# TPT02.net
KiCad netlist of a schematic drawn in EAGLE
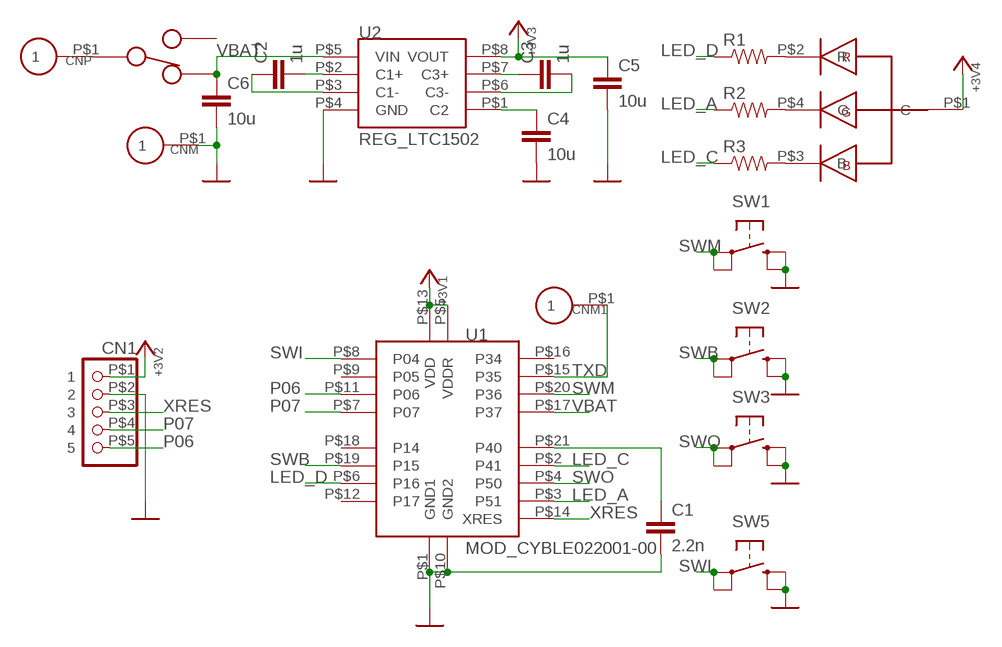
[diagram p0: schematic, sheet 1]

(export (version "E")
  (design (tool "Eeschema 10.0.6"))
  (components
    (comp (ref "C1")
      (value "2.2n")
      (footprint "eagle-import:0603")
      (libsource (lib "eagle-import") (part "CAP0603"))
    )
    (comp (ref "C2")
      (value "1u")
      (footprint "eagle-import:0603")
      (libsource (lib "eagle-import") (part "CAP0603"))
    )
    (comp (ref "C3")
      (value "1u")
      (footprint "eagle-import:0603")
      (libsource (lib "eagle-import") (part "CAP0603"))
    )
    (comp (ref "C4")
      (value "10u")
      (footprint "eagle-import:0603")
      (libsource (lib "eagle-import") (part "CAP0603"))
    )
    (comp (ref "C5")
      (value "10u")
      (footprint "eagle-import:0603")
      (libsource (lib "eagle-import") (part "CAP0603"))
    )
    (comp (ref "C6")
      (value "10u")
      (footprint "eagle-import:0603")
      (libsource (lib "eagle-import") (part "CAP0603"))
    )
    (comp (ref "CN1")
      (value "CON_PINHD-1X550MIL")
      (footprint "eagle-import:1X5_50MIL")
      (libsource (lib "eagle-import") (part "CON_PINHD-1X550MIL"))
    )
    (comp (ref "CNM")
      (value "CON_P01SMD1MM")
      (footprint "eagle-import:PAD_SMD1MM")
      (libsource (lib "eagle-import") (part "CON_P01SMD1MM"))
    )
    (comp (ref "CNM1")
      (value "CON_P01SMD1MM")
      (footprint "eagle-import:PAD_SMD1MM")
      (libsource (lib "eagle-import") (part "CON_P01SMD1MM"))
    )
    (comp (ref "CNP")
      (value "CON_P01SMD1MM")
      (footprint "eagle-import:PAD_SMD1MM")
      (libsource (lib "eagle-import") (part "CON_P01SMD1MM"))
    )
    (comp (ref "D1")
      (value "LED_RGB_OSTB0603C1C")
      (footprint "eagle-import:LED_0606_4P")
      (libsource (lib "eagle-import") (part "LED_RGB_OSTB0603C1C"))
    )
    (comp (ref "R1")
      (value "RES0603")
      (footprint "eagle-import:0603")
      (libsource (lib "eagle-import") (part "RES0603"))
    )
    (comp (ref "R2")
      (value "RES0603")
      (footprint "eagle-import:0603")
      (libsource (lib "eagle-import") (part "RES0603"))
    )
    (comp (ref "R3")
      (value "RES0603")
      (footprint "eagle-import:0603")
      (libsource (lib "eagle-import") (part "RES0603"))
    )
    (comp (ref "SW1")
      (value "SW_TACTEVQP2")
      (footprint "eagle-import:SW_EVQP2")
      (libsource (lib "eagle-import") (part "SW_TACTEVQP2"))
    )
    (comp (ref "SW2")
      (value "SW_TACTPTS525SK08")
      (footprint "eagle-import:SW_PTS525SK08")
      (libsource (lib "eagle-import") (part "SW_TACTPTS525SK08"))
    )
    (comp (ref "SW3")
      (value "SW_TACTPTS525SK08")
      (footprint "eagle-import:SW_PTS525SK08")
      (libsource (lib "eagle-import") (part "SW_TACTPTS525SK08"))
    )
    (comp (ref "SW4")
      (value "SW_SLIDECUS12")
      (footprint "eagle-import:SW_CUS-12B")
      (libsource (lib "eagle-import") (part "SW_SLIDECUS12"))
    )
    (comp (ref "SW5")
      (value "SW_TACTEVQPU02")
      (footprint "eagle-import:SW_EVQPUA02")
      (libsource (lib "eagle-import") (part "SW_TACTEVQPU02"))
    )
    (comp (ref "U1")
      (value "MOD_CYBLE022001-00")
      (footprint "eagle-import:MOD_CYBLE022001-00")
      (libsource (lib "eagle-import") (part "MOD_CYBLE022001-00"))
    )
    (comp (ref "U2")
      (value "REG_LTC1502")
      (footprint "eagle-import:MSOP8")
      (libsource (lib "eagle-import") (part "REG_LTC1502"))
    )
  )
  (nets
    (net (code "1") (name "/LED_A") (class "Default")
      (node (ref "R2") (pin "1") (pinfunction "1_1") (pintype "passive"))
      (node (ref "U1") (pin "P$3") (pinfunction "P51_P$3") (pintype "bidirectional"))
    )
    (net (code "2") (name "/LED_C") (class "Default")
      (node (ref "R3") (pin "1") (pinfunction "1_1") (pintype "passive"))
      (node (ref "U1") (pin "P$2") (pinfunction "P41_P$2") (pintype "bidirectional"))
    )
    (net (code "3") (name "/LED_D") (class "Default")
      (node (ref "R1") (pin "1") (pinfunction "1_1") (pintype "passive"))
      (node (ref "U1") (pin "P$6") (pinfunction "P16_P$6") (pintype "bidirectional"))
    )
    (net (code "4") (name "/P$3") (class "Default")
      (node (ref "SW4") (pin "P$3") (pinfunction "P$3_P$3") (pintype "power_in"))
    )
    (net (code "5") (name "/P06") (class "Default")
      (node (ref "CN1") (pin "P$5") (pinfunction "5_P$5") (pintype "passive"))
      (node (ref "U1") (pin "P$11") (pinfunction "P06_P$11") (pintype "bidirectional"))
    )
    (net (code "6") (name "/P07") (class "Default")
      (node (ref "CN1") (pin "P$4") (pinfunction "4_P$4") (pintype "passive"))
      (node (ref "U1") (pin "P$7") (pinfunction "P07_P$7") (pintype "bidirectional"))
    )
    (net (code "7") (name "/SWB") (class "Default")
      (node (ref "SW2") (pin "P$A1") (pinfunction "P_P$A1") (pintype "passive"))
      (node (ref "SW2") (pin "P$A2") (pinfunction "P1_P$A2") (pintype "passive"))
      (node (ref "U1") (pin "P$19") (pinfunction "P15_P$19") (pintype "bidirectional"))
    )
    (net (code "8") (name "/SWI") (class "Default")
      (node (ref "SW5") (pin "PA1") (pinfunction "P_PA1") (pintype "passive"))
      (node (ref "SW5") (pin "PA2") (pinfunction "P1_PA2") (pintype "passive"))
      (node (ref "U1") (pin "P$8") (pinfunction "P04_P$8") (pintype "bidirectional"))
    )
    (net (code "9") (name "/SWM") (class "Default")
      (node (ref "SW1") (pin "PA1") (pinfunction "P_PA1") (pintype "passive"))
      (node (ref "SW1") (pin "PA2") (pinfunction "P1_PA2") (pintype "passive"))
      (node (ref "U1") (pin "P$20") (pinfunction "P36_P$20") (pintype "bidirectional"))
    )
    (net (code "10") (name "/SWO") (class "Default")
      (node (ref "SW3") (pin "P$A1") (pinfunction "P_P$A1") (pintype "passive"))
      (node (ref "SW3") (pin "P$A2") (pinfunction "P1_P$A2") (pintype "passive"))
      (node (ref "U1") (pin "P$4") (pinfunction "P50_P$4") (pintype "bidirectional"))
    )
    (net (code "11") (name "/TXD") (class "Default")
      (node (ref "CNM1") (pin "P$1") (pinfunction "1_P$1") (pintype "bidirectional"))
      (node (ref "U1") (pin "P$15") (pinfunction "P35_P$15") (pintype "bidirectional"))
    )
    (net (code "12") (name "/VBAT") (class "Default")
      (node (ref "C6") (pin "1") (pinfunction "1_1") (pintype "passive"))
      (node (ref "SW4") (pin "P$1") (pinfunction "P$1_P$1") (pintype "power_in"))
      (node (ref "U1") (pin "P$17") (pinfunction "P37_P$17") (pintype "bidirectional"))
      (node (ref "U2") (pin "P$5") (pinfunction "VIN_P$5") (pintype "bidirectional"))
    )
    (net (code "13") (name "/XRES") (class "Default")
      (node (ref "CN1") (pin "P$3") (pinfunction "3_P$3") (pintype "passive"))
      (node (ref "U1") (pin "P$14") (pinfunction "XRES_P$14") (pintype "bidirectional"))
    )
    (net (code "14") (name "Net-(CNP-1)") (class "Default")
      (node (ref "CNP") (pin "P$1") (pinfunction "1_P$1") (pintype "bidirectional"))
      (node (ref "SW4") (pin "P$2") (pinfunction "P$2_P$2") (pintype "power_in"))
    )
    (net (code "15") (name "Net-(D1-B)") (class "Default")
      (node (ref "D1") (pin "P$3") (pinfunction "B_P$3") (pintype "bidirectional"))
      (node (ref "R3") (pin "2") (pinfunction "2_2") (pintype "passive"))
    )
    (net (code "16") (name "Net-(D1-G)") (class "Default")
      (node (ref "D1") (pin "P$4") (pinfunction "G_P$4") (pintype "bidirectional"))
      (node (ref "R2") (pin "2") (pinfunction "2_2") (pintype "passive"))
    )
    (net (code "17") (name "Net-(D1-R)") (class "Default")
      (node (ref "D1") (pin "P$2") (pinfunction "R_P$2") (pintype "bidirectional"))
      (node (ref "R1") (pin "2") (pinfunction "2_2") (pintype "passive"))
    )
    (net (code "18") (name "Net-(U1-P40)") (class "Default")
      (node (ref "C1") (pin "1") (pinfunction "1_1") (pintype "passive"))
      (node (ref "U1") (pin "P$21") (pinfunction "P40_P$21") (pintype "bidirectional"))
    )
    (net (code "19") (name "Net-(U2-C1+)") (class "Default")
      (node (ref "C2") (pin "2") (pinfunction "2_2") (pintype "passive"))
      (node (ref "U2") (pin "P$2") (pinfunction "C1+_P$2") (pintype "bidirectional"))
    )
    (net (code "20") (name "Net-(U2-C1-)") (class "Default")
      (node (ref "C2") (pin "1") (pinfunction "1_1") (pintype "passive"))
      (node (ref "U2") (pin "P$3") (pinfunction "C1-_P$3") (pintype "bidirectional"))
    )
    (net (code "21") (name "Net-(U2-C2)") (class "Default")
      (node (ref "C4") (pin "1") (pinfunction "1_1") (pintype "passive"))
      (node (ref "U2") (pin "P$1") (pinfunction "C2_P$1") (pintype "bidirectional"))
    )
    (net (code "22") (name "Net-(U2-C3+)") (class "Default")
      (node (ref "C3") (pin "1") (pinfunction "1_1") (pintype "passive"))
      (node (ref "U2") (pin "P$7") (pinfunction "C3+_P$7") (pintype "bidirectional"))
    )
    (net (code "23") (name "Net-(U2-C3-)") (class "Default")
      (node (ref "C3") (pin "2") (pinfunction "2_2") (pintype "passive"))
      (node (ref "U2") (pin "P$6") (pinfunction "C3-_P$6") (pintype "bidirectional"))
    )
    (net (code "24") (name "POW_+3V3") (class "Default")
      (node (ref "C5") (pin "1") (pinfunction "1_1") (pintype "passive"))
      (node (ref "CN1") (pin "P$1") (pinfunction "1_P$1") (pintype "passive"))
      (node (ref "D1") (pin "P$1") (pinfunction "C_P$1") (pintype "bidirectional"))
      (node (ref "U1") (pin "P$13") (pinfunction "VDD_P$13") (pintype "bidirectional"))
      (node (ref "U1") (pin "P$5") (pinfunction "VDDR_P$5") (pintype "bidirectional"))
      (node (ref "U2") (pin "P$8") (pinfunction "VOUT_P$8") (pintype "bidirectional"))
    )
    (net (code "25") (name "POW_GND") (class "Default")
      (node (ref "C1") (pin "2") (pinfunction "2_2") (pintype "passive"))
      (node (ref "C4") (pin "2") (pinfunction "2_2") (pintype "passive"))
      (node (ref "C5") (pin "2") (pinfunction "2_2") (pintype "passive"))
      (node (ref "C6") (pin "2") (pinfunction "2_2") (pintype "passive"))
      (node (ref "CN1") (pin "P$2") (pinfunction "2_P$2") (pintype "passive"))
      (node (ref "CNM") (pin "P$1") (pinfunction "1_P$1") (pintype "bidirectional"))
      (node (ref "SW1") (pin "PB1") (pinfunction "S_PB1") (pintype "passive"))
      (node (ref "SW1") (pin "PB2") (pinfunction "S1_PB2") (pintype "passive"))
      (node (ref "SW2") (pin "P$B1") (pinfunction "S_P$B1") (pintype "passive"))
      (node (ref "SW2") (pin "P$B2") (pinfunction "S1_P$B2") (pintype "passive"))
      (node (ref "SW3") (pin "P$B1") (pinfunction "S_P$B1") (pintype "passive"))
      (node (ref "SW3") (pin "P$B2") (pinfunction "S1_P$B2") (pintype "passive"))
      (node (ref "SW5") (pin "PB1") (pinfunction "S_PB1") (pintype "passive"))
      (node (ref "SW5") (pin "PB2") (pinfunction "S1_PB2") (pintype "passive"))
      (node (ref "U1") (pin "P$1") (pinfunction "GND1_P$1") (pintype "bidirectional"))
      (node (ref "U1") (pin "P$10") (pinfunction "GND2_P$10") (pintype "bidirectional"))
      (node (ref "U2") (pin "P$4") (pinfunction "GND_P$4") (pintype "bidirectional"))
    )
    (net (code "26") (name "unconnected-(U1-P05-PadP$9)") (class "Default")
      (node (ref "U1") (pin "P$9") (pinfunction "P05_P$9") (pintype "bidirectional"))
    )
    (net (code "27") (name "unconnected-(U1-P14-PadP$18)") (class "Default")
      (node (ref "U1") (pin "P$18") (pinfunction "P14_P$18") (pintype "bidirectional"))
    )
    (net (code "28") (name "unconnected-(U1-P17-PadP$12)") (class "Default")
      (node (ref "U1") (pin "P$12") (pinfunction "P17_P$12") (pintype "bidirectional"))
    )
    (net (code "29") (name "unconnected-(U1-P34-PadP$16)") (class "Default")
      (node (ref "U1") (pin "P$16") (pinfunction "P34_P$16") (pintype "bidirectional"))
    )
  )
)
